# esp5V.net
KiCad netlist of a schematic drawn in EAGLE
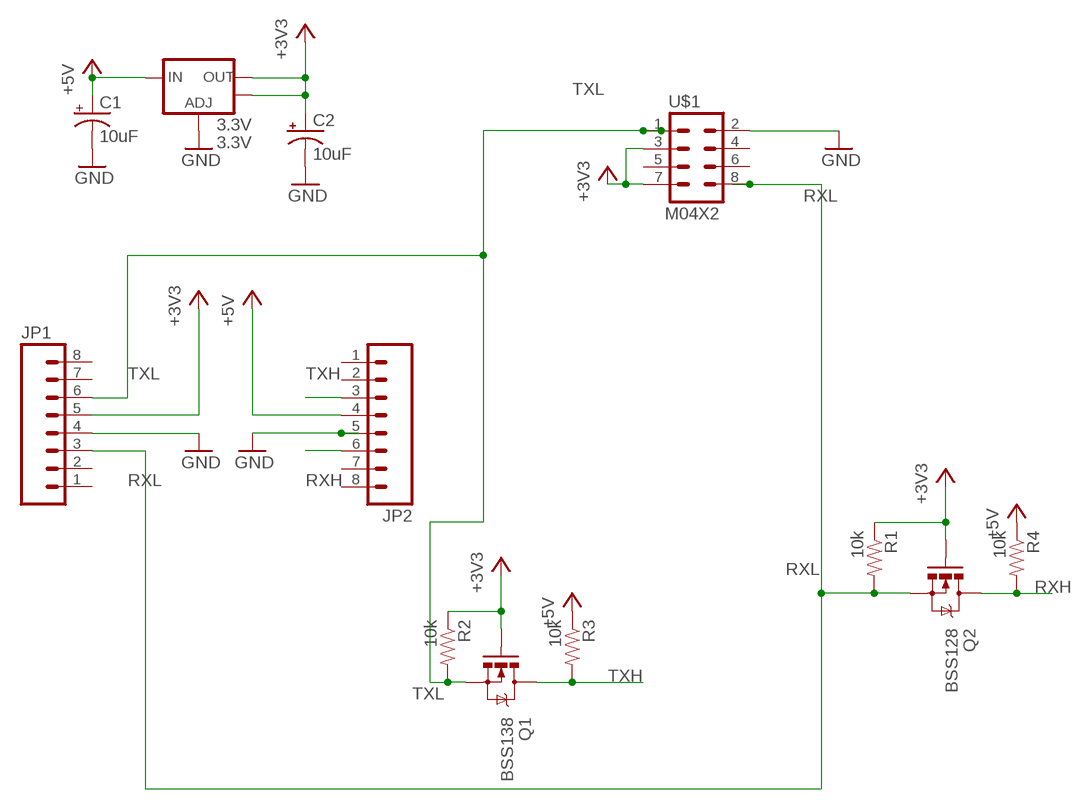
[diagram p0: schematic, sheet 1]

(export (version "E")
  (design (tool "Eeschema 10.0.6"))
  (components
    (comp (ref "3.3V")
      (value "3.3V")
      (footprint "eagle-import:SOT223")
      (libsource (lib "eagle-import") (part "V_REG_LM1117SOT223"))
    )
    (comp (ref "C1")
      (value "10uF")
      (footprint "eagle-import:EIA3216")
      (libsource (lib "eagle-import") (part "10UF-16V-10%(TANT)"))
    )
    (comp (ref "C2")
      (value "10uF")
      (footprint "eagle-import:EIA3216")
      (libsource (lib "eagle-import") (part "10UF-16V-10%(TANT)"))
    )
    (comp (ref "JP1")
      (value "M08NO_SILK")
      (footprint "eagle-import:1X08_NO_SILK")
      (libsource (lib "eagle-import") (part "M08NO_SILK"))
    )
    (comp (ref "JP2")
      (value "M08NO_SILK")
      (footprint "eagle-import:1X08_NO_SILK")
      (libsource (lib "eagle-import") (part "M08NO_SILK"))
    )
    (comp (ref "Q1")
      (value "BSS138")
      (footprint "eagle-import:SOT23-3")
      (libsource (lib "eagle-import") (part "MOSFET-NCHANNELBSS138"))
    )
    (comp (ref "Q2")
      (value "BSS128")
      (footprint "eagle-import:SOT23-3")
      (libsource (lib "eagle-import") (part "MOSFET-NCHANNELBSS138"))
    )
    (comp (ref "R1")
      (value "10k")
      (footprint "eagle-import:0805")
      (libsource (lib "eagle-import") (part "0.22OHM1/4W1%(0805)"))
    )
    (comp (ref "R2")
      (value "10k")
      (footprint "eagle-import:0805")
      (libsource (lib "eagle-import") (part "0.22OHM1/4W1%(0805)"))
    )
    (comp (ref "R3")
      (value "10k")
      (footprint "eagle-import:0805")
      (libsource (lib "eagle-import") (part "0.22OHM1/4W1%(0805)"))
    )
    (comp (ref "R4")
      (value "10k")
      (footprint "eagle-import:0805")
      (libsource (lib "eagle-import") (part "0.22OHM1/4W1%(0805)"))
    )
    (comp (ref "U$1")
      (value "M04X2")
      (footprint "eagle-import:2X4")
      (libsource (lib "eagle-import") (part "M04X2"))
    )
  )
  (nets
    (net (code "1") (name "+3V3") (class "Default")
      (node (ref "3.3V") (pin "2") (pinfunction "OUT_2") (pintype "output"))
      (node (ref "3.3V") (pin "4") (pinfunction "OUT_4") (pintype "output"))
      (node (ref "C2") (pin "A") (pinfunction "+_A") (pintype "passive"))
      (node (ref "JP1") (pin "5") (pinfunction "5_5") (pintype "passive"))
      (node (ref "Q1") (pin "1") (pinfunction "G_1") (pintype "passive"))
      (node (ref "Q2") (pin "1") (pinfunction "G_1") (pintype "passive"))
      (node (ref "R1") (pin "1") (pinfunction "1_1") (pintype "passive"))
      (node (ref "R2") (pin "1") (pinfunction "1_1") (pintype "passive"))
      (node (ref "U$1") (pin "3") (pinfunction "3_3") (pintype "passive"))
      (node (ref "U$1") (pin "7") (pinfunction "7_7") (pintype "passive"))
    )
    (net (code "2") (name "+5V") (class "Default")
      (node (ref "3.3V") (pin "3") (pinfunction "IN_3") (pintype "input"))
      (node (ref "C1") (pin "A") (pinfunction "+_A") (pintype "passive"))
      (node (ref "JP2") (pin "4") (pinfunction "4_4") (pintype "passive"))
      (node (ref "R3") (pin "1") (pinfunction "1_1") (pintype "passive"))
      (node (ref "R4") (pin "1") (pinfunction "1_1") (pintype "passive"))
    )
    (net (code "3") (name "/RXH") (class "Default")
      (node (ref "JP2") (pin "6") (pinfunction "6_6") (pintype "passive"))
      (node (ref "Q2") (pin "3") (pinfunction "D_3") (pintype "passive"))
      (node (ref "R4") (pin "2") (pinfunction "2_2") (pintype "passive"))
    )
    (net (code "4") (name "/RXL") (class "Default")
      (node (ref "JP1") (pin "3") (pinfunction "3_3") (pintype "passive"))
      (node (ref "Q2") (pin "2") (pinfunction "S_2") (pintype "passive"))
      (node (ref "R1") (pin "2") (pinfunction "2_2") (pintype "passive"))
      (node (ref "U$1") (pin "8") (pinfunction "8_8") (pintype "passive"))
    )
    (net (code "5") (name "/TXH") (class "Default")
      (node (ref "JP2") (pin "3") (pinfunction "3_3") (pintype "passive"))
      (node (ref "Q1") (pin "3") (pinfunction "D_3") (pintype "passive"))
      (node (ref "R3") (pin "2") (pinfunction "2_2") (pintype "passive"))
    )
    (net (code "6") (name "/TXL") (class "Default")
      (node (ref "JP1") (pin "6") (pinfunction "6_6") (pintype "passive"))
      (node (ref "Q1") (pin "2") (pinfunction "S_2") (pintype "passive"))
      (node (ref "R2") (pin "2") (pinfunction "2_2") (pintype "passive"))
      (node (ref "U$1") (pin "1") (pinfunction "1_1") (pintype "passive"))
    )
    (net (code "7") (name "GND") (class "Default")
      (node (ref "3.3V") (pin "1") (pinfunction "ADJ_1") (pintype "input"))
      (node (ref "C1") (pin "C") (pinfunction "-_C") (pintype "passive"))
      (node (ref "C2") (pin "C") (pinfunction "-_C") (pintype "passive"))
      (node (ref "JP1") (pin "4") (pinfunction "4_4") (pintype "passive"))
      (node (ref "JP2") (pin "5") (pinfunction "5_5") (pintype "passive"))
      (node (ref "U$1") (pin "2") (pinfunction "2_2") (pintype "passive"))
    )
    (net (code "8") (name "unconnected-(JP1-Pad1)") (class "Default")
      (node (ref "JP1") (pin "1") (pinfunction "1_1") (pintype "passive"))
    )
    (net (code "9") (name "unconnected-(JP1-Pad2)") (class "Default")
      (node (ref "JP1") (pin "2") (pinfunction "2_2") (pintype "passive"))
    )
    (net (code "10") (name "unconnected-(JP1-Pad7)") (class "Default")
      (node (ref "JP1") (pin "7") (pinfunction "7_7") (pintype "passive"))
    )
    (net (code "11") (name "unconnected-(JP1-Pad8)") (class "Default")
      (node (ref "JP1") (pin "8") (pinfunction "8_8") (pintype "passive"))
    )
    (net (code "12") (name "unconnected-(JP2-Pad1)") (class "Default")
      (node (ref "JP2") (pin "1") (pinfunction "1_1") (pintype "passive"))
    )
    (net (code "13") (name "unconnected-(JP2-Pad2)") (class "Default")
      (node (ref "JP2") (pin "2") (pinfunction "2_2") (pintype "passive"))
    )
    (net (code "14") (name "unconnected-(JP2-Pad7)") (class "Default")
      (node (ref "JP2") (pin "7") (pinfunction "7_7") (pintype "passive"))
    )
    (net (code "15") (name "unconnected-(JP2-Pad8)") (class "Default")
      (node (ref "JP2") (pin "8") (pinfunction "8_8") (pintype "passive"))
    )
    (net (code "16") (name "unconnected-(U$1-Pad4)") (class "Default")
      (node (ref "U$1") (pin "4") (pinfunction "4_4") (pintype "passive"))
    )
    (net (code "17") (name "unconnected-(U$1-Pad5)") (class "Default")
      (node (ref "U$1") (pin "5") (pinfunction "5_5") (pintype "passive"))
    )
    (net (code "18") (name "unconnected-(U$1-Pad6)") (class "Default")
      (node (ref "U$1") (pin "6") (pinfunction "6_6") (pintype "passive"))
    )
  )
)
